# THP_Sensor.net
KiCad netlist of a schematic drawn in Altium Designer
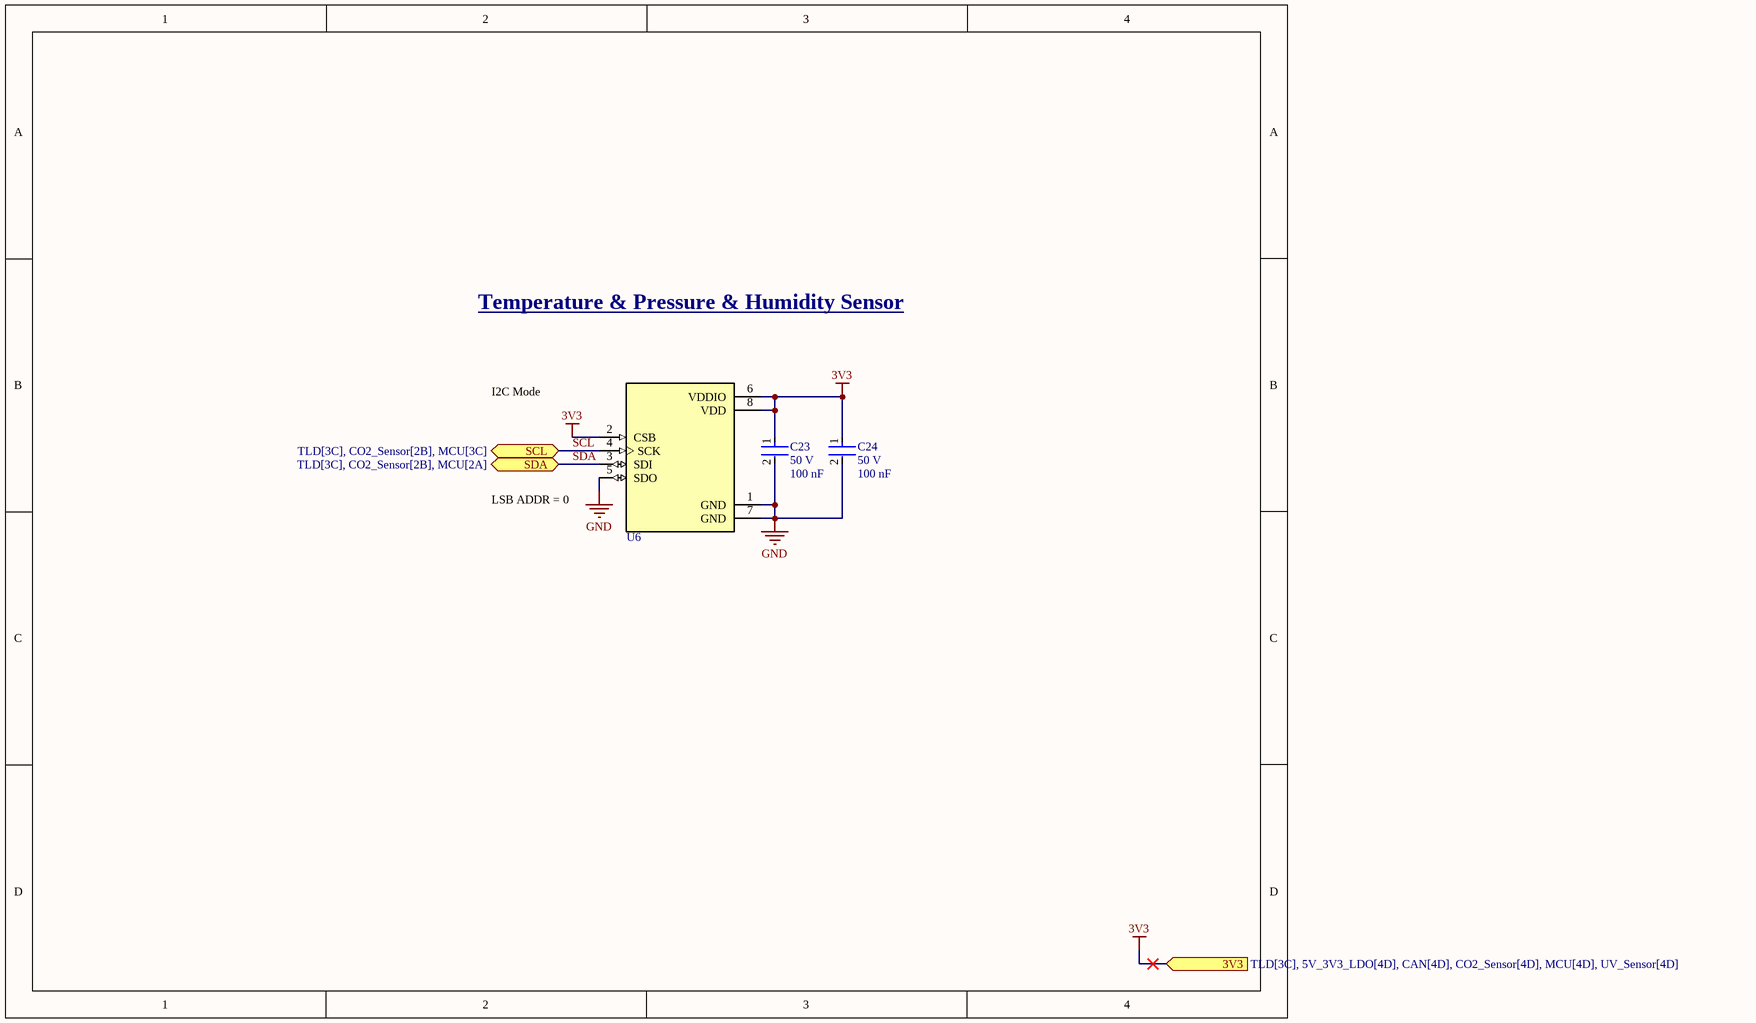
[diagram p0: THP_Sensor.SchDoc]

(export (version "E")
  (design (tool "Eeschema 10.0.6"))
  (components
    (comp (ref "C23")
      (value "CC0805KRX7R9BB104")
      (footprint "CAP-0805")
      (description "CAP CER 0.1UF 50V X7R 0805")
      (fields (field (name "VOLTAGE RATING") "50 V") (field (name "CAPACITANCE") "100 nF"))
      (libsource (lib "JLC_25") (part "CAP-0.1U-0002"))
    )
    (comp (ref "C24")
      (value "CC0805KRX7R9BB104")
      (footprint "CAP-0805")
      (description "CAP CER 0.1UF 50V X7R 0805")
      (fields (field (name "VOLTAGE RATING") "50 V") (field (name "CAPACITANCE") "100 nF"))
      (libsource (lib "JLC_25") (part "CAP-0.1U-0002"))
    )
    (comp (ref "U6")
      (value "BME280")
      (footprint "PSON65P250X250X100-8N")
      (libsource (lib "MasterLib") (part "SENS-Temp-Press-Humid"))
    )
  )
  (nets
    (net (code "1") (name "/SCL") (class "Default")
      (node (ref "U6") (pin "4") (pinfunction "SCK_4") (pintype "input"))
    )
    (net (code "2") (name "/SDA") (class "Default")
      (node (ref "U6") (pin "3") (pinfunction "SDI_3") (pintype "bidirectional"))
    )
    (net (code "3") (name "3V3") (class "Default")
      (node (ref "C23") (pin "1") (pinfunction "1_1") (pintype "passive"))
      (node (ref "C24") (pin "1") (pinfunction "1_1") (pintype "passive"))
      (node (ref "U6") (pin "2") (pinfunction "CSB_2") (pintype "input"))
      (node (ref "U6") (pin "6") (pinfunction "VDDIO_6") (pintype "power_in"))
      (node (ref "U6") (pin "8") (pinfunction "VDD_8") (pintype "power_in"))
    )
    (net (code "4") (name "GND") (class "Default")
      (node (ref "C23") (pin "2") (pinfunction "2_2") (pintype "passive"))
      (node (ref "C24") (pin "2") (pinfunction "2_2") (pintype "passive"))
      (node (ref "U6") (pin "1") (pinfunction "GND_1") (pintype "power_in"))
      (node (ref "U6") (pin "5") (pinfunction "SDO_5") (pintype "bidirectional"))
      (node (ref "U6") (pin "7") (pinfunction "GND_7") (pintype "power_in"))
    )
  )
)
